# WWIII-02.net
KiCad netlist of a schematic drawn in EAGLE
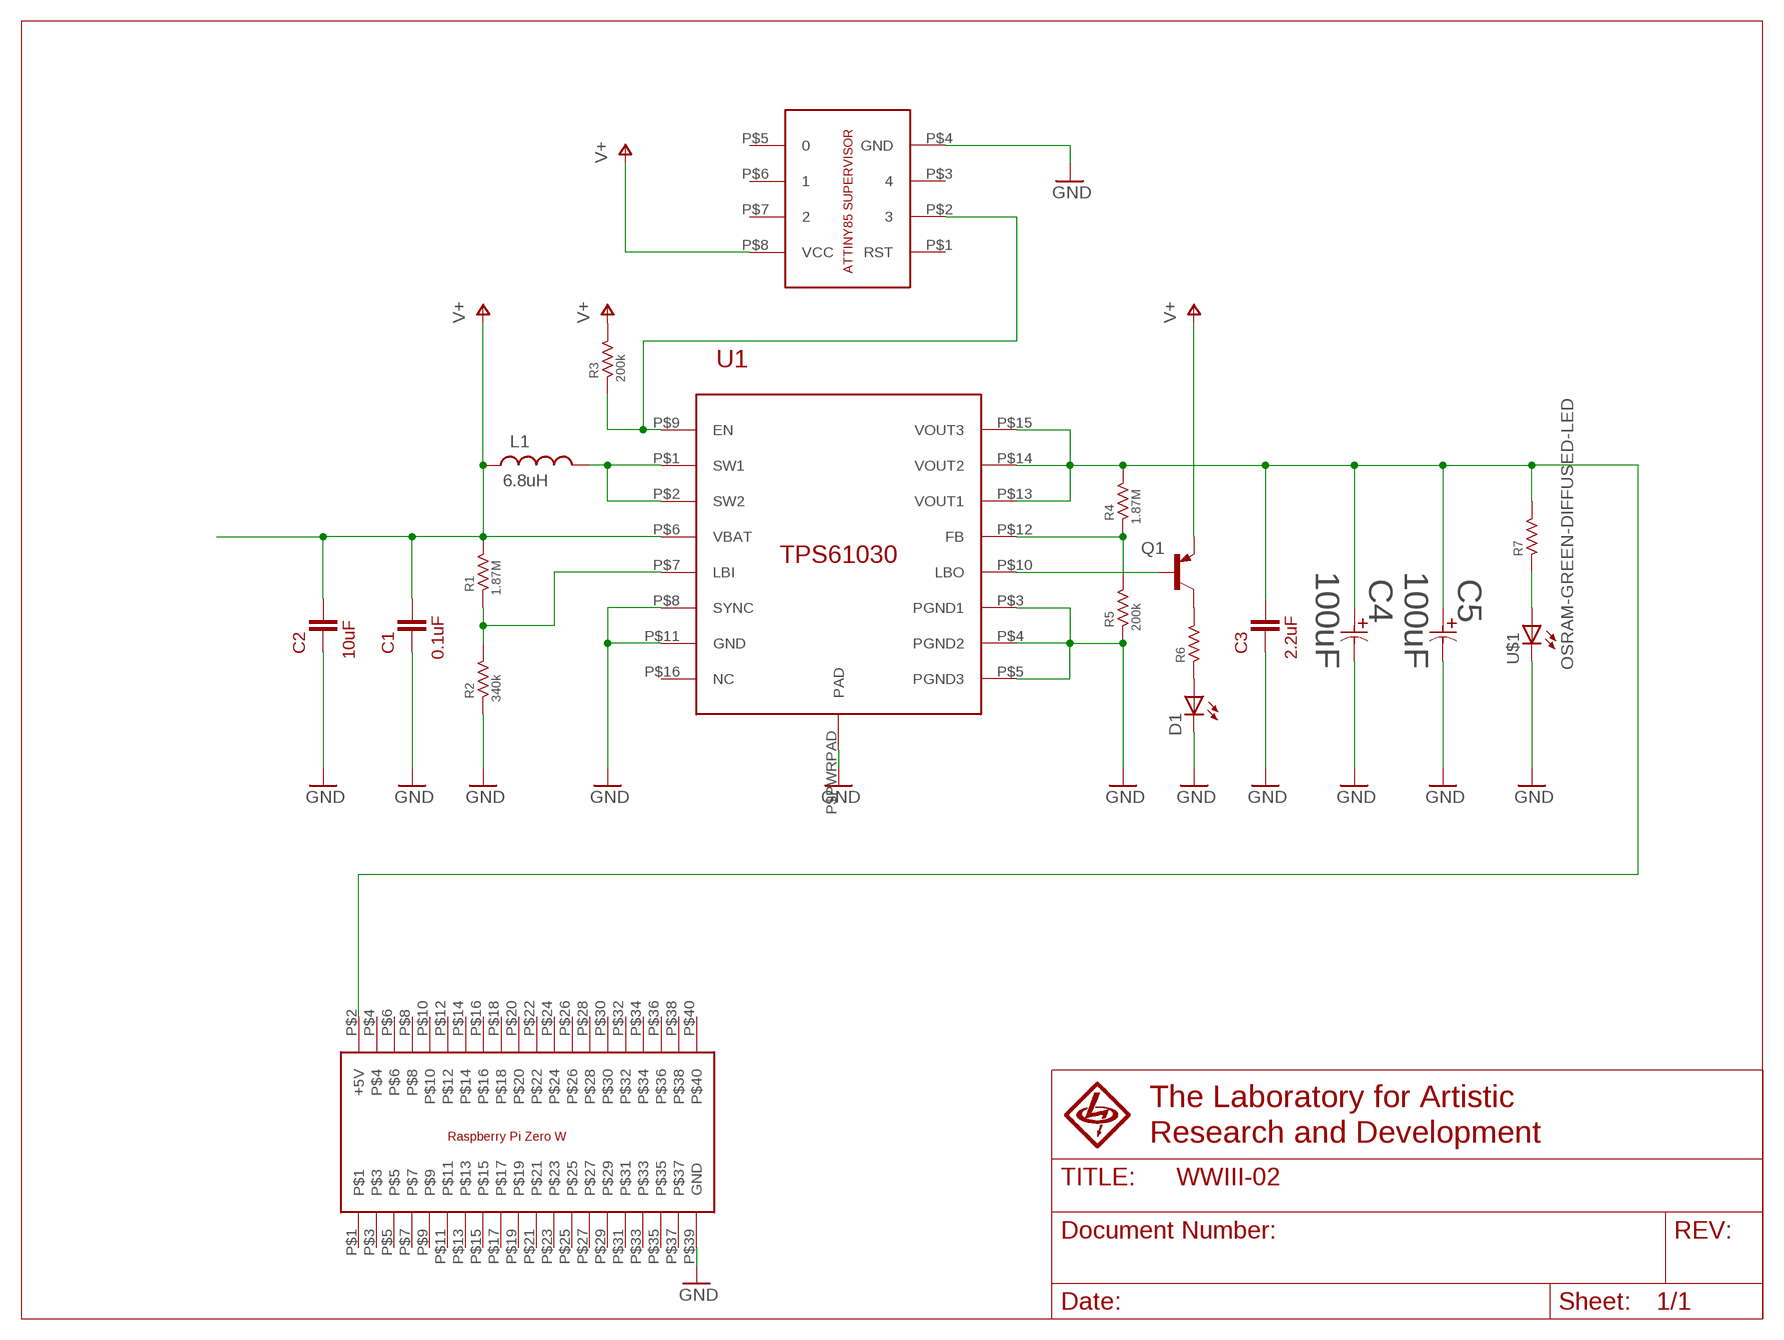
[diagram p0: schematic, sheet 1]

(export (version "E")
  (design (tool "Eeschema 10.0.6"))
  (components
    (comp (ref "C1")
      (value "0.1uF")
      (footprint "eagle-import:0805")
      (fields (field (name "MANUFACTURER_PART_NUMBER") "08055C104KAT2A"))
      (libsource (lib "eagle-import") (part "AVX-SMD-CERAMIC-CAPACITOR-0805-0.1UF"))
    )
    (comp (ref "C2")
      (value "10uF")
      (footprint "eagle-import:KEM_C1006_X5R_SMD")
      (libsource (lib "eagle-import") (part "KEMET-SMD-CERAMIC-CAPACITOR-10UF"))
    )
    (comp (ref "C3")
      (value "2.2uF")
      (footprint "eagle-import:CAP-X5R")
      (libsource (lib "eagle-import") (part "TAIYO-SMD-CERAMIC-CAPACITOR-0805-2.2UF"))
    )
    (comp (ref "C4")
      (value "100uF")
      (footprint "eagle-import:CAP_EEE_C")
      (fields (field (name "MANUFACTURER_PART_NUMBER") "EEE1AA101WR"))
      (libsource (lib "eagle-import") (part "PANASONIC-SMD-ELECTROLYTIC-CAPACITOR-100UF"))
    )
    (comp (ref "C5")
      (value "100uF")
      (footprint "eagle-import:CAP_EEE_C")
      (fields (field (name "MANUFACTURER_PART_NUMBER") "EEE1AA101WR"))
      (libsource (lib "eagle-import") (part "PANASONIC-SMD-ELECTROLYTIC-CAPACITOR-100UF"))
    )
    (comp (ref "D1")
      (value "OSRAM-RED-DIFFUSED-LED")
      (footprint "eagle-import:OSRAM_CHIPLED")
      (libsource (lib "eagle-import") (part "OSRAM-RED-DIFFUSED-LED"))
    )
    (comp (ref "L1")
      (value "6.8uH")
      (footprint "eagle-import:MLZ2012")
      (libsource (lib "eagle-import") (part "TDK-SMD-FIXED-INDUCTOR"))
    )
    (comp (ref "Q1")
      (value "ON-SEMI-SMD-PREBIAS-TRANS-SOT23")
      (footprint "eagle-import:SOT23-3")
      (libsource (lib "eagle-import") (part "ON-SEMI-SMD-PREBIAS-TRANS-SOT23"))
    )
    (comp (ref "R1")
      (value "1.87M")
      (footprint "eagle-import:RC0805N")
      (fields (field (name "MANUFACTURER_PART_NUMBER") "RC0805JR0710KL"))
      (libsource (lib "eagle-import") (part "YAGEO-SMD-1/8W-RESISTOR-0805"))
    )
    (comp (ref "R2")
      (value "340k")
      (footprint "eagle-import:RC0805N")
      (fields (field (name "MANUFACTURER_PART_NUMBER") "RC0805JR0710KL"))
      (libsource (lib "eagle-import") (part "YAGEO-SMD-1/8W-RESISTOR-0805"))
    )
    (comp (ref "R3")
      (value "200k")
      (footprint "eagle-import:RESISTOR-0805")
      (libsource (lib "eagle-import") (part "STACKPOLE-SMD-1/8W-RESISTOR-0805"))
    )
    (comp (ref "R4")
      (value "1.87M")
      (footprint "eagle-import:PANASONIC-SMD-RESISTOR-0805")
      (libsource (lib "eagle-import") (part "PANASONIC-SMD-RESISTOR-0805-1.87M"))
    )
    (comp (ref "R5")
      (value "200k")
      (footprint "eagle-import:RESISTOR-0805")
      (libsource (lib "eagle-import") (part "STACKPOLE-SMD-1/8W-RESISTOR-0805"))
    )
    (comp (ref "R6")
      (value "YAGEO-SMD-1/8W-RESISTOR-0805")
      (footprint "eagle-import:RC0805N")
      (fields (field (name "MANUFACTURER_PART_NUMBER") "RC0805JR0710KL"))
      (libsource (lib "eagle-import") (part "YAGEO-SMD-1/8W-RESISTOR-0805"))
    )
    (comp (ref "R7")
      (value "YAGEO-SMD-1/8W-RESISTOR-0805")
      (footprint "eagle-import:RC0805N")
      (fields (field (name "MANUFACTURER_PART_NUMBER") "RC0805JR0710KL"))
      (libsource (lib "eagle-import") (part "YAGEO-SMD-1/8W-RESISTOR-0805"))
    )
    (comp (ref "U$1")
      (value "OSRAM-GREEN-DIFFUSED-LED")
      (footprint "eagle-import:OSRAM_CHIPLED")
      (libsource (lib "eagle-import") (part "OSRAM-GREEN-DIFFUSED-LED"))
    )
    (comp (ref "U1")
      (value "TPS61030")
      (footprint "eagle-import:TPS61030PWPR")
      (libsource (lib "eagle-import") (part "TPS61030"))
    )
    (comp (ref "U2")
      (value "RASPBERRY-PI")
      (footprint "eagle-import:RASPBERRY-PI")
      (libsource (lib "eagle-import") (part "RASPBERRY-PI"))
    )
    (comp (ref "U3")
      (value "ATTINY-SUPERVISOR")
      (footprint "eagle-import:ATTINY-SOCKETED")
      (libsource (lib "eagle-import") (part "ATTINY-SUPERVISOR"))
    )
  )
  (nets
    (net (code "1") (name "GND") (class "Default")
      (node (ref "C1") (pin "1") (pinfunction "1_1") (pintype "passive"))
      (node (ref "C2") (pin "1") (pinfunction "1_1") (pintype "passive"))
      (node (ref "C3") (pin "1") (pinfunction "1_1") (pintype "passive"))
      (node (ref "C4") (pin "2") (pinfunction "22_2") (pintype "passive"))
      (node (ref "C5") (pin "2") (pinfunction "22_2") (pintype "passive"))
      (node (ref "D1") (pin "P$2") (pinfunction "2_P$2") (pintype "output"))
      (node (ref "R2") (pin "1") (pinfunction "P$1_1") (pintype "passive"))
      (node (ref "R5") (pin "1") (pinfunction "P$1_1") (pintype "passive"))
      (node (ref "U$1") (pin "P$2") (pinfunction "2_P$2") (pintype "output"))
      (node (ref "U1") (pin "P$11") (pinfunction "GND_P$11") (pintype "bidirectional"))
      (node (ref "U1") (pin "P$3") (pinfunction "PGND1_P$3") (pintype "bidirectional"))
      (node (ref "U1") (pin "P$4") (pinfunction "PGND2_P$4") (pintype "bidirectional"))
      (node (ref "U1") (pin "P$5") (pinfunction "PGND3_P$5") (pintype "bidirectional"))
      (node (ref "U1") (pin "P$8") (pinfunction "SYNC_P$8") (pintype "bidirectional"))
      (node (ref "U1") (pin "P$PWRPAD") (pinfunction "PAD_P$PWRPAD") (pintype "bidirectional"))
      (node (ref "U2") (pin "P$39") (pinfunction "GND_P$39") (pintype "bidirectional"))
      (node (ref "U3") (pin "P$4") (pinfunction "GND_P$4") (pintype "bidirectional"))
    )
    (net (code "2") (name "Net-(C4-11)") (class "Default")
      (node (ref "C3") (pin "2") (pinfunction "2_2") (pintype "passive"))
      (node (ref "C4") (pin "1") (pinfunction "11_1") (pintype "passive"))
      (node (ref "C5") (pin "1") (pinfunction "11_1") (pintype "passive"))
      (node (ref "R4") (pin "P$2") (pinfunction "P$2_P$2") (pintype "passive"))
      (node (ref "R7") (pin "2") (pinfunction "P$2_2") (pintype "passive"))
      (node (ref "U1") (pin "P$13") (pinfunction "VOUT1_P$13") (pintype "bidirectional"))
      (node (ref "U1") (pin "P$14") (pinfunction "VOUT2_P$14") (pintype "bidirectional"))
      (node (ref "U1") (pin "P$15") (pinfunction "VOUT3_P$15") (pintype "bidirectional"))
      (node (ref "U2") (pin "P$2") (pinfunction "+5V_P$2") (pintype "bidirectional"))
    )
    (net (code "3") (name "Net-(D1-1)") (class "Default")
      (node (ref "D1") (pin "P$1") (pinfunction "1_P$1") (pintype "input"))
      (node (ref "R6") (pin "1") (pinfunction "P$1_1") (pintype "passive"))
    )
    (net (code "4") (name "Net-(R1-P$1)") (class "Default")
      (node (ref "R1") (pin "1") (pinfunction "P$1_1") (pintype "passive"))
      (node (ref "R2") (pin "2") (pinfunction "P$2_2") (pintype "passive"))
      (node (ref "U1") (pin "P$7") (pinfunction "LBI_P$7") (pintype "bidirectional"))
    )
    (net (code "5") (name "Net-(R3-P$1)") (class "Default")
      (node (ref "R3") (pin "1") (pinfunction "P$1_1") (pintype "passive"))
      (node (ref "U1") (pin "P$9") (pinfunction "EN_P$9") (pintype "bidirectional"))
      (node (ref "U3") (pin "P$2") (pinfunction "3_P$2") (pintype "bidirectional"))
    )
    (net (code "6") (name "Net-(R5-P$2)") (class "Default")
      (node (ref "R4") (pin "P$1") (pinfunction "P$1_P$1") (pintype "passive"))
      (node (ref "R5") (pin "2") (pinfunction "P$2_2") (pintype "passive"))
      (node (ref "U1") (pin "P$12") (pinfunction "FB_P$12") (pintype "bidirectional"))
    )
    (net (code "7") (name "Net-(R6-P$2)") (class "Default")
      (node (ref "Q1") (pin "3") (pinfunction "3_3") (pintype "passive"))
      (node (ref "R6") (pin "2") (pinfunction "P$2_2") (pintype "passive"))
    )
    (net (code "8") (name "Net-(R7-P$1)") (class "Default")
      (node (ref "R7") (pin "1") (pinfunction "P$1_1") (pintype "passive"))
      (node (ref "U$1") (pin "P$1") (pinfunction "1_P$1") (pintype "input"))
    )
    (net (code "9") (name "Net-(U1-LBO)") (class "Default")
      (node (ref "Q1") (pin "1") (pinfunction "1_1") (pintype "passive"))
      (node (ref "U1") (pin "P$10") (pinfunction "LBO_P$10") (pintype "bidirectional"))
    )
    (net (code "10") (name "Net-(U1-SW1)") (class "Default")
      (node (ref "L1") (pin "2") (pinfunction "2_2") (pintype "passive"))
      (node (ref "U1") (pin "P$1") (pinfunction "SW1_P$1") (pintype "bidirectional"))
      (node (ref "U1") (pin "P$2") (pinfunction "SW2_P$2") (pintype "input"))
    )
    (net (code "11") (name "V+") (class "Default")
      (node (ref "C1") (pin "2") (pinfunction "2_2") (pintype "passive"))
      (node (ref "C2") (pin "2") (pinfunction "2_2") (pintype "passive"))
      (node (ref "L1") (pin "1") (pinfunction "1_1") (pintype "passive"))
      (node (ref "Q1") (pin "2") (pinfunction "2_2") (pintype "passive"))
      (node (ref "R1") (pin "2") (pinfunction "P$2_2") (pintype "passive"))
      (node (ref "R3") (pin "2") (pinfunction "P$2_2") (pintype "passive"))
      (node (ref "U1") (pin "P$6") (pinfunction "VBAT_P$6") (pintype "bidirectional"))
      (node (ref "U3") (pin "P$8") (pinfunction "VCC_P$8") (pintype "bidirectional"))
    )
    (net (code "12") (name "unconnected-(U1-NC-PadP$16)") (class "Default")
      (node (ref "U1") (pin "P$16") (pinfunction "NC_P$16") (pintype "no_connect"))
    )
    (net (code "13") (name "unconnected-(U2-PadP$1)") (class "Default")
      (node (ref "U2") (pin "P$1") (pinfunction "P$1_P$1") (pintype "bidirectional"))
    )
    (net (code "14") (name "unconnected-(U2-PadP$3)") (class "Default")
      (node (ref "U2") (pin "P$3") (pinfunction "P$3_P$3") (pintype "bidirectional"))
    )
    (net (code "15") (name "unconnected-(U2-PadP$4)") (class "Default")
      (node (ref "U2") (pin "P$4") (pinfunction "P$4_P$4") (pintype "bidirectional"))
    )
    (net (code "16") (name "unconnected-(U2-PadP$5)") (class "Default")
      (node (ref "U2") (pin "P$5") (pinfunction "P$5_P$5") (pintype "bidirectional"))
    )
    (net (code "17") (name "unconnected-(U2-PadP$6)") (class "Default")
      (node (ref "U2") (pin "P$6") (pinfunction "P$6_P$6") (pintype "bidirectional"))
    )
    (net (code "18") (name "unconnected-(U2-PadP$7)") (class "Default")
      (node (ref "U2") (pin "P$7") (pinfunction "P$7_P$7") (pintype "bidirectional"))
    )
    (net (code "19") (name "unconnected-(U2-PadP$8)") (class "Default")
      (node (ref "U2") (pin "P$8") (pinfunction "P$8_P$8") (pintype "bidirectional"))
    )
    (net (code "20") (name "unconnected-(U2-PadP$9)") (class "Default")
      (node (ref "U2") (pin "P$9") (pinfunction "P$9_P$9") (pintype "bidirectional"))
    )
    (net (code "21") (name "unconnected-(U2-PadP$10)") (class "Default")
      (node (ref "U2") (pin "P$10") (pinfunction "P$10_P$10") (pintype "bidirectional"))
    )
    (net (code "22") (name "unconnected-(U2-PadP$11)") (class "Default")
      (node (ref "U2") (pin "P$11") (pinfunction "P$11_P$11") (pintype "bidirectional"))
    )
    (net (code "23") (name "unconnected-(U2-PadP$12)") (class "Default")
      (node (ref "U2") (pin "P$12") (pinfunction "P$12_P$12") (pintype "bidirectional"))
    )
    (net (code "24") (name "unconnected-(U2-PadP$13)") (class "Default")
      (node (ref "U2") (pin "P$13") (pinfunction "P$13_P$13") (pintype "bidirectional"))
    )
    (net (code "25") (name "unconnected-(U2-PadP$14)") (class "Default")
      (node (ref "U2") (pin "P$14") (pinfunction "P$14_P$14") (pintype "bidirectional"))
    )
    (net (code "26") (name "unconnected-(U2-PadP$15)") (class "Default")
      (node (ref "U2") (pin "P$15") (pinfunction "P$15_P$15") (pintype "bidirectional"))
    )
    (net (code "27") (name "unconnected-(U2-PadP$16)") (class "Default")
      (node (ref "U2") (pin "P$16") (pinfunction "P$16_P$16") (pintype "bidirectional"))
    )
    (net (code "28") (name "unconnected-(U2-PadP$17)") (class "Default")
      (node (ref "U2") (pin "P$17") (pinfunction "P$17_P$17") (pintype "bidirectional"))
    )
    (net (code "29") (name "unconnected-(U2-PadP$18)") (class "Default")
      (node (ref "U2") (pin "P$18") (pinfunction "P$18_P$18") (pintype "bidirectional"))
    )
    (net (code "30") (name "unconnected-(U2-PadP$19)") (class "Default")
      (node (ref "U2") (pin "P$19") (pinfunction "P$19_P$19") (pintype "bidirectional"))
    )
    (net (code "31") (name "unconnected-(U2-PadP$20)") (class "Default")
      (node (ref "U2") (pin "P$20") (pinfunction "P$20_P$20") (pintype "bidirectional"))
    )
    (net (code "32") (name "unconnected-(U2-PadP$21)") (class "Default")
      (node (ref "U2") (pin "P$21") (pinfunction "P$21_P$21") (pintype "bidirectional"))
    )
    (net (code "33") (name "unconnected-(U2-PadP$22)") (class "Default")
      (node (ref "U2") (pin "P$22") (pinfunction "P$22_P$22") (pintype "bidirectional"))
    )
    (net (code "34") (name "unconnected-(U2-PadP$23)") (class "Default")
      (node (ref "U2") (pin "P$23") (pinfunction "P$23_P$23") (pintype "bidirectional"))
    )
    (net (code "35") (name "unconnected-(U2-PadP$24)") (class "Default")
      (node (ref "U2") (pin "P$24") (pinfunction "P$24_P$24") (pintype "bidirectional"))
    )
    (net (code "36") (name "unconnected-(U2-PadP$25)") (class "Default")
      (node (ref "U2") (pin "P$25") (pinfunction "P$25_P$25") (pintype "bidirectional"))
    )
    (net (code "37") (name "unconnected-(U2-PadP$26)") (class "Default")
      (node (ref "U2") (pin "P$26") (pinfunction "P$26_P$26") (pintype "bidirectional"))
    )
    (net (code "38") (name "unconnected-(U2-PadP$27)") (class "Default")
      (node (ref "U2") (pin "P$27") (pinfunction "P$27_P$27") (pintype "bidirectional"))
    )
    (net (code "39") (name "unconnected-(U2-PadP$28)") (class "Default")
      (node (ref "U2") (pin "P$28") (pinfunction "P$28_P$28") (pintype "bidirectional"))
    )
    (net (code "40") (name "unconnected-(U2-PadP$29)") (class "Default")
      (node (ref "U2") (pin "P$29") (pinfunction "P$29_P$29") (pintype "bidirectional"))
    )
    (net (code "41") (name "unconnected-(U2-PadP$30)") (class "Default")
      (node (ref "U2") (pin "P$30") (pinfunction "P$30_P$30") (pintype "bidirectional"))
    )
    (net (code "42") (name "unconnected-(U2-PadP$31)") (class "Default")
      (node (ref "U2") (pin "P$31") (pinfunction "P$31_P$31") (pintype "bidirectional"))
    )
    (net (code "43") (name "unconnected-(U2-PadP$32)") (class "Default")
      (node (ref "U2") (pin "P$32") (pinfunction "P$32_P$32") (pintype "bidirectional"))
    )
    (net (code "44") (name "unconnected-(U2-PadP$33)") (class "Default")
      (node (ref "U2") (pin "P$33") (pinfunction "P$33_P$33") (pintype "bidirectional"))
    )
    (net (code "45") (name "unconnected-(U2-PadP$34)") (class "Default")
      (node (ref "U2") (pin "P$34") (pinfunction "P$34_P$34") (pintype "bidirectional"))
    )
    (net (code "46") (name "unconnected-(U2-PadP$35)") (class "Default")
      (node (ref "U2") (pin "P$35") (pinfunction "P$35_P$35") (pintype "bidirectional"))
    )
    (net (code "47") (name "unconnected-(U2-PadP$36)") (class "Default")
      (node (ref "U2") (pin "P$36") (pinfunction "P$36_P$36") (pintype "bidirectional"))
    )
    (net (code "48") (name "unconnected-(U2-PadP$37)") (class "Default")
      (node (ref "U2") (pin "P$37") (pinfunction "P$37_P$37") (pintype "bidirectional"))
    )
    (net (code "49") (name "unconnected-(U2-PadP$38)") (class "Default")
      (node (ref "U2") (pin "P$38") (pinfunction "P$38_P$38") (pintype "bidirectional"))
    )
    (net (code "50") (name "unconnected-(U2-PadP$40)") (class "Default")
      (node (ref "U2") (pin "P$40") (pinfunction "P$40_P$40") (pintype "bidirectional"))
    )
    (net (code "51") (name "unconnected-(U3-0-PadP$5)") (class "Default")
      (node (ref "U3") (pin "P$5") (pinfunction "0_P$5") (pintype "bidirectional"))
    )
    (net (code "52") (name "unconnected-(U3-1-PadP$6)") (class "Default")
      (node (ref "U3") (pin "P$6") (pinfunction "1_P$6") (pintype "bidirectional"))
    )
    (net (code "53") (name "unconnected-(U3-2-PadP$7)") (class "Default")
      (node (ref "U3") (pin "P$7") (pinfunction "2_P$7") (pintype "bidirectional"))
    )
    (net (code "54") (name "unconnected-(U3-4-PadP$3)") (class "Default")
      (node (ref "U3") (pin "P$3") (pinfunction "4_P$3") (pintype "bidirectional"))
    )
    (net (code "55") (name "unconnected-(U3-RST-PadP$1)") (class "Default")
      (node (ref "U3") (pin "P$1") (pinfunction "RST_P$1") (pintype "bidirectional"))
    )
  )
)
